# Schematic.net
KiCad netlist of a schematic drawn in Altium Designer
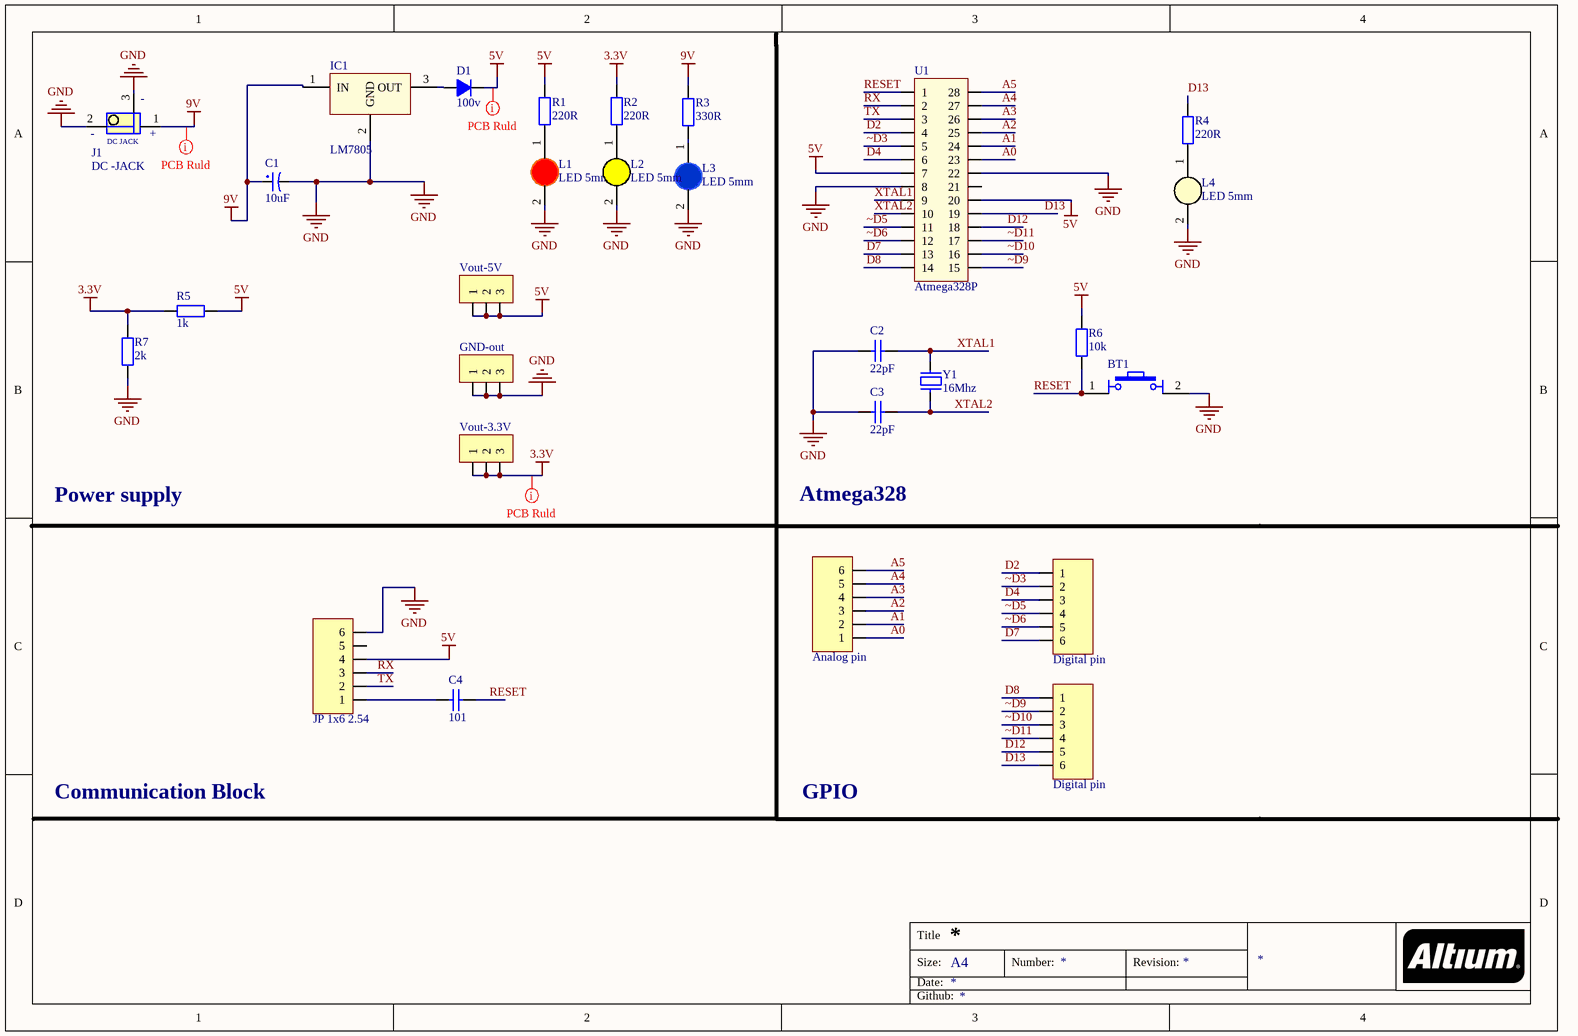
[diagram p0: Schematic.SchDoc]

(export (version "E")
  (design (tool "Eeschema 10.0.6"))
  (components
    (comp (ref "BT1")
      (value "Nut Nhan 4 Chan Cam 6x6")
      (footprint "Nut Nhan 4 Chan Cam 6x6")
      (description "Nut Nhan 4 Chan 6x6mm")
      (libsource (lib "Altium_Lib_by_KhueNguyenCreator") (part "Nut Nhan 4 Chan Cam 6x6"))
    )
    (comp (ref "C1")
      (value "10uF")
      (footprint "tu hoa 4mm")
      (description "Cắm")
      (libsource (lib "Altium_Lib_by_KhueNguyenCreator") (part "Tu Hoa 10uF 25V 4x7"))
    )
    (comp (ref "C2")
      (value "22pF")
      (footprint "tu gom")
      (description "Cắm")
      (libsource (lib "Altium_Lib_by_KhueNguyenCreator") (part "Tu gom 22pF 50V"))
    )
    (comp (ref "C3")
      (value "22pF")
      (footprint "tu gom")
      (description "Cắm")
      (libsource (lib "Altium_Lib_by_KhueNguyenCreator") (part "Tu gom 22pF 50V"))
    )
    (comp (ref "C4")
      (value "101")
      (footprint "tu gom")
      (description "Cắm")
      (libsource (lib "Altium_Lib_by_KhueNguyenCreator") (part "Tu gom 101 50V"))
    )
    (comp (ref "D1")
      (value "100v")
      (footprint "DIODE 1A")
      (description "Cắm")
      (libsource (lib "Altium_Lib_by_KhueNguyenCreator") (part "Diode 1N4007"))
    )
    (comp (ref "GND-out")
      (value "JP 1x3 2.54")
      (footprint "JP 1x3 DT")
      (description "Cắm")
      (libsource (lib "Altium_Lib_by_KhueNguyenCreator") (part "JP 1x3 2.54 Duc Thang"))
    )
    (comp (ref "IC1")
      (value "LM7805")
      (footprint "QTO-220")
      (description "On ap +, from + 5 to + 24VDC")
      (libsource (lib "syhaunguyen") (part "LM78xx"))
    )
    (comp (ref "J1")
      (value "DC -JACK")
      (footprint "CON3_129_PJ-002A_TH_RA")
      (description "3 Pins, 1 Row 228mil Pitch, right angle Connector, male")
      (fields (field (name "MANUFACTURER") "JST") (field (name "MANUFACTURER PART NUMBER") "PJ-002A"))
      (libsource (lib "Altium_Lib_by_KhueNguyenCreator") (part "CON-PLG_3X1-228-DC_JACK"))
    )
    (comp (ref "JP1")
      (value "Digital pin")
      (footprint "JP 1x6 CT")
      (description "Cắm")
      (libsource (lib "Altium_Lib_by_KhueNguyenCreator") (part "JP 1x6 2.54 Cai Thang"))
    )
    (comp (ref "JP2")
      (value "Analog pin")
      (footprint "JP 1x6 CT")
      (description "Cắm")
      (libsource (lib "") (part "JP 1x6 2.54 Cai Thang_1"))
    )
    (comp (ref "JP3")
      (value "JP 1x6 2.54")
      (footprint "JP 1x6 CC")
      (description "Cắm")
      (libsource (lib "Altium_Lib_by_KhueNguyenCreator") (part "JP 1x6 2.54 Cai Cong"))
    )
    (comp (ref "JP4")
      (value "Digital pin")
      (footprint "JP 1x6 CT")
      (description "Cắm")
      (libsource (lib "Altium_Lib_by_KhueNguyenCreator") (part "JP 1x6 2.54 Cai Thang"))
    )
    (comp (ref "L1")
      (value "LED 5mm")
      (footprint "LED-5MM-RED")
      (description "Cắm")
      (libsource (lib "Altium_Lib_by_KhueNguyenCreator") (part "LED 5mm Do"))
    )
    (comp (ref "L2")
      (value "LED 5mm")
      (footprint "LED-5MM-Yellow")
      (description "Cắm")
      (libsource (lib "Altium_Lib_by_KhueNguyenCreator") (part "LED 5mm Vang"))
    )
    (comp (ref "L3")
      (value "LED 5mm")
      (footprint "LED-5MM-BLUE")
      (description "Cắm")
      (libsource (lib "Altium_Lib_by_KhueNguyenCreator") (part "LED 5mm Xanh Duong"))
    )
    (comp (ref "L4")
      (value "LED 5mm")
      (footprint "LED-5MM-WHITE")
      (description "Cắm")
      (libsource (lib "Altium_Lib_by_KhueNguyenCreator") (part "LED 5mm Trang"))
    )
    (comp (ref "R1")
      (value "220R")
      (footprint "tro vach 1/2w")
      (description "Cắm")
      (libsource (lib "Altium_Lib_by_KhueNguyenCreator") (part "Tro Vach 1/2W 5% 240R"))
    )
    (comp (ref "R2")
      (value "220R")
      (footprint "tro vach 1/2w")
      (description "Cắm")
      (libsource (lib "Altium_Lib_by_KhueNguyenCreator") (part "Tro Vach 1/2W 5% 240R"))
    )
    (comp (ref "R3")
      (value "330R")
      (footprint "tro vach 1/2w")
      (description "Cắm")
      (libsource (lib "Altium_Lib_by_KhueNguyenCreator") (part "Tro Vach 1/2W 5% 330R"))
    )
    (comp (ref "R4")
      (value "220R")
      (footprint "tro vach 1/2w")
      (description "Cắm")
      (libsource (lib "Altium_Lib_by_KhueNguyenCreator") (part "Tro Vach 1/2W 5% 240R"))
    )
    (comp (ref "R5")
      (value "1k")
      (footprint "tro vach 1/2w")
      (description "Cắm")
      (libsource (lib "Altium_Lib_by_KhueNguyenCreator") (part "Tro Vach 1/2W 5% 1k"))
    )
    (comp (ref "R6")
      (value "10k")
      (footprint "tro vach 1/2w")
      (description "Cắm")
      (libsource (lib "Altium_Lib_by_KhueNguyenCreator") (part "Tro Vach 1/2W 5% 10k"))
    )
    (comp (ref "R7")
      (value "2k")
      (footprint "tro vach 1/4w")
      (description "Cắm")
      (libsource (lib "Altium_Lib_by_KhueNguyenCreator") (part "Tro Vach 1/4W 5% 2k"))
    )
    (comp (ref "U1")
      (value "Atmega328P")
      (footprint "DIP28/W0.3")
      (description "DIP28")
      (libsource (lib "syhaunguyen") (part "DIP28"))
    )
    (comp (ref "Vout-3.3V")
      (value "JP 1x3 2.54")
      (footprint "JP 1x3 DT")
      (description "Cắm")
      (libsource (lib "Altium_Lib_by_KhueNguyenCreator") (part "JP 1x3 2.54 Duc Thang"))
    )
    (comp (ref "Vout-5V")
      (value "JP 1x3 2.54")
      (footprint "JP 1x3 DT")
      (description "Cắm")
      (libsource (lib "Altium_Lib_by_KhueNguyenCreator") (part "JP 1x3 2.54 Duc Thang"))
    )
    (comp (ref "Y1")
      (value "16Mhz")
      (footprint "Thach Anh 2 chan cam")
      (description "Crystal For all Crystal 2pin.")
      (libsource (lib "Altium_Lib_by_KhueNguyenCreator") (part "Thach Anh 2 chan Cam"))
    )
  )
  (nets
    (net (code "1") (name "/A0") (class "Default")
      (node (ref "JP2") (pin "1") (pinfunction "1_1") (pintype "passive"))
      (node (ref "U1") (pin "23") (pinfunction "23_23") (pintype "passive"))
    )
    (net (code "2") (name "/A1") (class "Default")
      (node (ref "JP2") (pin "2") (pinfunction "2_2") (pintype "passive"))
      (node (ref "U1") (pin "24") (pinfunction "24_24") (pintype "passive"))
    )
    (net (code "3") (name "/A2") (class "Default")
      (node (ref "JP2") (pin "3") (pinfunction "3_3") (pintype "passive"))
      (node (ref "U1") (pin "25") (pinfunction "25_25") (pintype "passive"))
    )
    (net (code "4") (name "/A3") (class "Default")
      (node (ref "JP2") (pin "4") (pinfunction "4_4") (pintype "passive"))
      (node (ref "U1") (pin "26") (pinfunction "26_26") (pintype "passive"))
    )
    (net (code "5") (name "/A4") (class "Default")
      (node (ref "JP2") (pin "5") (pinfunction "5_5") (pintype "passive"))
      (node (ref "U1") (pin "27") (pinfunction "27_27") (pintype "passive"))
    )
    (net (code "6") (name "/A5") (class "Default")
      (node (ref "JP2") (pin "6") (pinfunction "6_6") (pintype "passive"))
      (node (ref "U1") (pin "28") (pinfunction "28_28") (pintype "passive"))
    )
    (net (code "7") (name "/D2") (class "Default")
      (node (ref "JP1") (pin "1") (pinfunction "1_1") (pintype "passive"))
      (node (ref "U1") (pin "4") (pinfunction "4_4") (pintype "passive"))
    )
    (net (code "8") (name "/D4") (class "Default")
      (node (ref "JP1") (pin "3") (pinfunction "3_3") (pintype "passive"))
      (node (ref "U1") (pin "6") (pinfunction "6_6") (pintype "passive"))
    )
    (net (code "9") (name "/D7") (class "Default")
      (node (ref "JP1") (pin "6") (pinfunction "6_6") (pintype "passive"))
      (node (ref "U1") (pin "13") (pinfunction "13_13") (pintype "passive"))
    )
    (net (code "10") (name "/D8") (class "Default")
      (node (ref "JP4") (pin "1") (pinfunction "1_1") (pintype "passive"))
      (node (ref "U1") (pin "14") (pinfunction "14_14") (pintype "passive"))
    )
    (net (code "11") (name "/D12") (class "Default")
      (node (ref "JP4") (pin "5") (pinfunction "5_5") (pintype "passive"))
      (node (ref "U1") (pin "18") (pinfunction "18_18") (pintype "passive"))
    )
    (net (code "12") (name "/D13") (class "Default")
      (node (ref "JP4") (pin "6") (pinfunction "6_6") (pintype "passive"))
      (node (ref "R4") (pin "2") (pinfunction "2_2") (pintype "passive"))
      (node (ref "U1") (pin "19") (pinfunction "19_19") (pintype "passive"))
    )
    (net (code "13") (name "/RESET") (class "Default")
      (node (ref "BT1") (pin "1") (pintype "passive"))
      (node (ref "C4") (pin "1") (pinfunction "1_1") (pintype "passive"))
      (node (ref "R6") (pin "1") (pinfunction "1_1") (pintype "passive"))
      (node (ref "U1") (pin "1") (pinfunction "1_1") (pintype "passive"))
    )
    (net (code "14") (name "/RX") (class "Default")
      (node (ref "JP3") (pin "3") (pinfunction "3_3") (pintype "passive"))
      (node (ref "U1") (pin "2") (pinfunction "2_2") (pintype "passive"))
    )
    (net (code "15") (name "/TX") (class "Default")
      (node (ref "JP3") (pin "2") (pinfunction "2_2") (pintype "passive"))
      (node (ref "U1") (pin "3") (pinfunction "3_3") (pintype "passive"))
    )
    (net (code "16") (name "/XTAL1") (class "Default")
      (node (ref "C2") (pin "1") (pinfunction "1_1") (pintype "passive"))
      (node (ref "U1") (pin "9") (pinfunction "9_9") (pintype "passive"))
      (node (ref "Y1") (pin "2") (pinfunction "2_2") (pintype "passive"))
    )
    (net (code "17") (name "/XTAL2") (class "Default")
      (node (ref "C3") (pin "1") (pinfunction "1_1") (pintype "passive"))
      (node (ref "U1") (pin "10") (pinfunction "10_10") (pintype "passive"))
      (node (ref "Y1") (pin "1") (pinfunction "1_1") (pintype "passive"))
    )
    (net (code "18") (name "/~D3") (class "Default")
      (node (ref "JP1") (pin "2") (pinfunction "2_2") (pintype "passive"))
      (node (ref "U1") (pin "5") (pinfunction "5_5") (pintype "passive"))
    )
    (net (code "19") (name "/~D5") (class "Default")
      (node (ref "JP1") (pin "4") (pinfunction "4_4") (pintype "passive"))
      (node (ref "U1") (pin "11") (pinfunction "11_11") (pintype "passive"))
    )
    (net (code "20") (name "/~D6") (class "Default")
      (node (ref "JP1") (pin "5") (pinfunction "5_5") (pintype "passive"))
      (node (ref "U1") (pin "12") (pinfunction "12_12") (pintype "passive"))
    )
    (net (code "21") (name "/~D9") (class "Default")
      (node (ref "JP4") (pin "2") (pinfunction "2_2") (pintype "passive"))
      (node (ref "U1") (pin "15") (pinfunction "15_15") (pintype "passive"))
    )
    (net (code "22") (name "/~D10") (class "Default")
      (node (ref "JP4") (pin "3") (pinfunction "3_3") (pintype "passive"))
      (node (ref "U1") (pin "16") (pinfunction "16_16") (pintype "passive"))
    )
    (net (code "23") (name "/~D11") (class "Default")
      (node (ref "JP4") (pin "4") (pinfunction "4_4") (pintype "passive"))
      (node (ref "U1") (pin "17") (pinfunction "17_17") (pintype "passive"))
    )
    (net (code "24") (name "3.3V") (class "Default")
      (node (ref "R2") (pin "2") (pinfunction "2_2") (pintype "passive"))
      (node (ref "R5") (pin "1") (pinfunction "1_1") (pintype "passive"))
      (node (ref "R7") (pin "2") (pinfunction "2_2") (pintype "passive"))
      (node (ref "Vout-3.3V") (pin "1") (pinfunction "1_1") (pintype "passive"))
      (node (ref "Vout-3.3V") (pin "2") (pinfunction "2_2") (pintype "passive"))
      (node (ref "Vout-3.3V") (pin "3") (pinfunction "3_3") (pintype "passive"))
    )
    (net (code "25") (name "5V") (class "Default")
      (node (ref "D1") (pin "2") (pinfunction "K_2") (pintype "passive"))
      (node (ref "JP3") (pin "4") (pinfunction "4_4") (pintype "passive"))
      (node (ref "R1") (pin "2") (pinfunction "2_2") (pintype "passive"))
      (node (ref "R5") (pin "2") (pinfunction "2_2") (pintype "passive"))
      (node (ref "R6") (pin "2") (pinfunction "2_2") (pintype "passive"))
      (node (ref "U1") (pin "20") (pinfunction "20_20") (pintype "passive"))
      (node (ref "U1") (pin "7") (pinfunction "7_7") (pintype "passive"))
      (node (ref "Vout-5V") (pin "1") (pinfunction "1_1") (pintype "passive"))
      (node (ref "Vout-5V") (pin "2") (pinfunction "2_2") (pintype "passive"))
      (node (ref "Vout-5V") (pin "3") (pinfunction "3_3") (pintype "passive"))
    )
    (net (code "26") (name "9V") (class "Default")
      (node (ref "C1") (pin "1") (pinfunction "1_1") (pintype "passive"))
      (node (ref "IC1") (pin "1") (pinfunction "IN_1") (pintype "passive"))
      (node (ref "J1") (pin "1") (pinfunction "1_1") (pintype "passive"))
      (node (ref "R3") (pin "2") (pinfunction "2_2") (pintype "passive"))
    )
    (net (code "27") (name "GND") (class "Default")
      (node (ref "BT1") (pin "2") (pintype "passive"))
      (node (ref "C1") (pin "2") (pinfunction "2_2") (pintype "passive"))
      (node (ref "C2") (pin "2") (pinfunction "2_2") (pintype "passive"))
      (node (ref "C3") (pin "2") (pinfunction "2_2") (pintype "passive"))
      (node (ref "GND-out") (pin "1") (pinfunction "1_1") (pintype "passive"))
      (node (ref "GND-out") (pin "2") (pinfunction "2_2") (pintype "passive"))
      (node (ref "GND-out") (pin "3") (pinfunction "3_3") (pintype "passive"))
      (node (ref "IC1") (pin "2") (pinfunction "GND_2") (pintype "passive"))
      (node (ref "J1") (pin "2") (pinfunction "2_2") (pintype "passive"))
      (node (ref "J1") (pin "3") (pinfunction "-_3") (pintype "passive"))
      (node (ref "JP3") (pin "6") (pinfunction "6_6") (pintype "passive"))
      (node (ref "L1") (pin "2") (pinfunction "K_2") (pintype "passive"))
      (node (ref "L2") (pin "2") (pinfunction "K_2") (pintype "passive"))
      (node (ref "L3") (pin "2") (pinfunction "K_2") (pintype "passive"))
      (node (ref "L4") (pin "2") (pinfunction "K_2") (pintype "passive"))
      (node (ref "R7") (pin "1") (pinfunction "1_1") (pintype "passive"))
      (node (ref "U1") (pin "22") (pinfunction "22_22") (pintype "passive"))
      (node (ref "U1") (pin "8") (pinfunction "8_8") (pintype "passive"))
    )
    (net (code "28") (name "Net-(C4-Pad2)") (class "Default")
      (node (ref "C4") (pin "2") (pinfunction "2_2") (pintype "passive"))
      (node (ref "JP3") (pin "1") (pinfunction "1_1") (pintype "passive"))
    )
    (net (code "29") (name "Net-(D1-A)") (class "Default")
      (node (ref "D1") (pin "1") (pinfunction "A_1") (pintype "passive"))
      (node (ref "IC1") (pin "3") (pinfunction "OUT_3") (pintype "passive"))
    )
    (net (code "30") (name "Net-(L1-A)") (class "Default")
      (node (ref "L1") (pin "1") (pinfunction "A_1") (pintype "passive"))
      (node (ref "R1") (pin "1") (pinfunction "1_1") (pintype "passive"))
    )
    (net (code "31") (name "Net-(L2-A)") (class "Default")
      (node (ref "L2") (pin "1") (pinfunction "A_1") (pintype "passive"))
      (node (ref "R2") (pin "1") (pinfunction "1_1") (pintype "passive"))
    )
    (net (code "32") (name "Net-(L3-A)") (class "Default")
      (node (ref "L3") (pin "1") (pinfunction "A_1") (pintype "passive"))
      (node (ref "R3") (pin "1") (pinfunction "1_1") (pintype "passive"))
    )
    (net (code "33") (name "Net-(L4-A)") (class "Default")
      (node (ref "L4") (pin "1") (pinfunction "A_1") (pintype "passive"))
      (node (ref "R4") (pin "1") (pinfunction "1_1") (pintype "passive"))
    )
    (net (code "34") (name "unconnected-(JP3-Pad5)") (class "Default")
      (node (ref "JP3") (pin "5") (pinfunction "5_5") (pintype "passive"))
    )
    (net (code "35") (name "unconnected-(U1-Pad21)") (class "Default")
      (node (ref "U1") (pin "21") (pinfunction "21_21") (pintype "passive"))
    )
  )
)
